# Arduino_ultrasonic_bjt.net
KiCad netlist of a schematic drawn in EAGLE
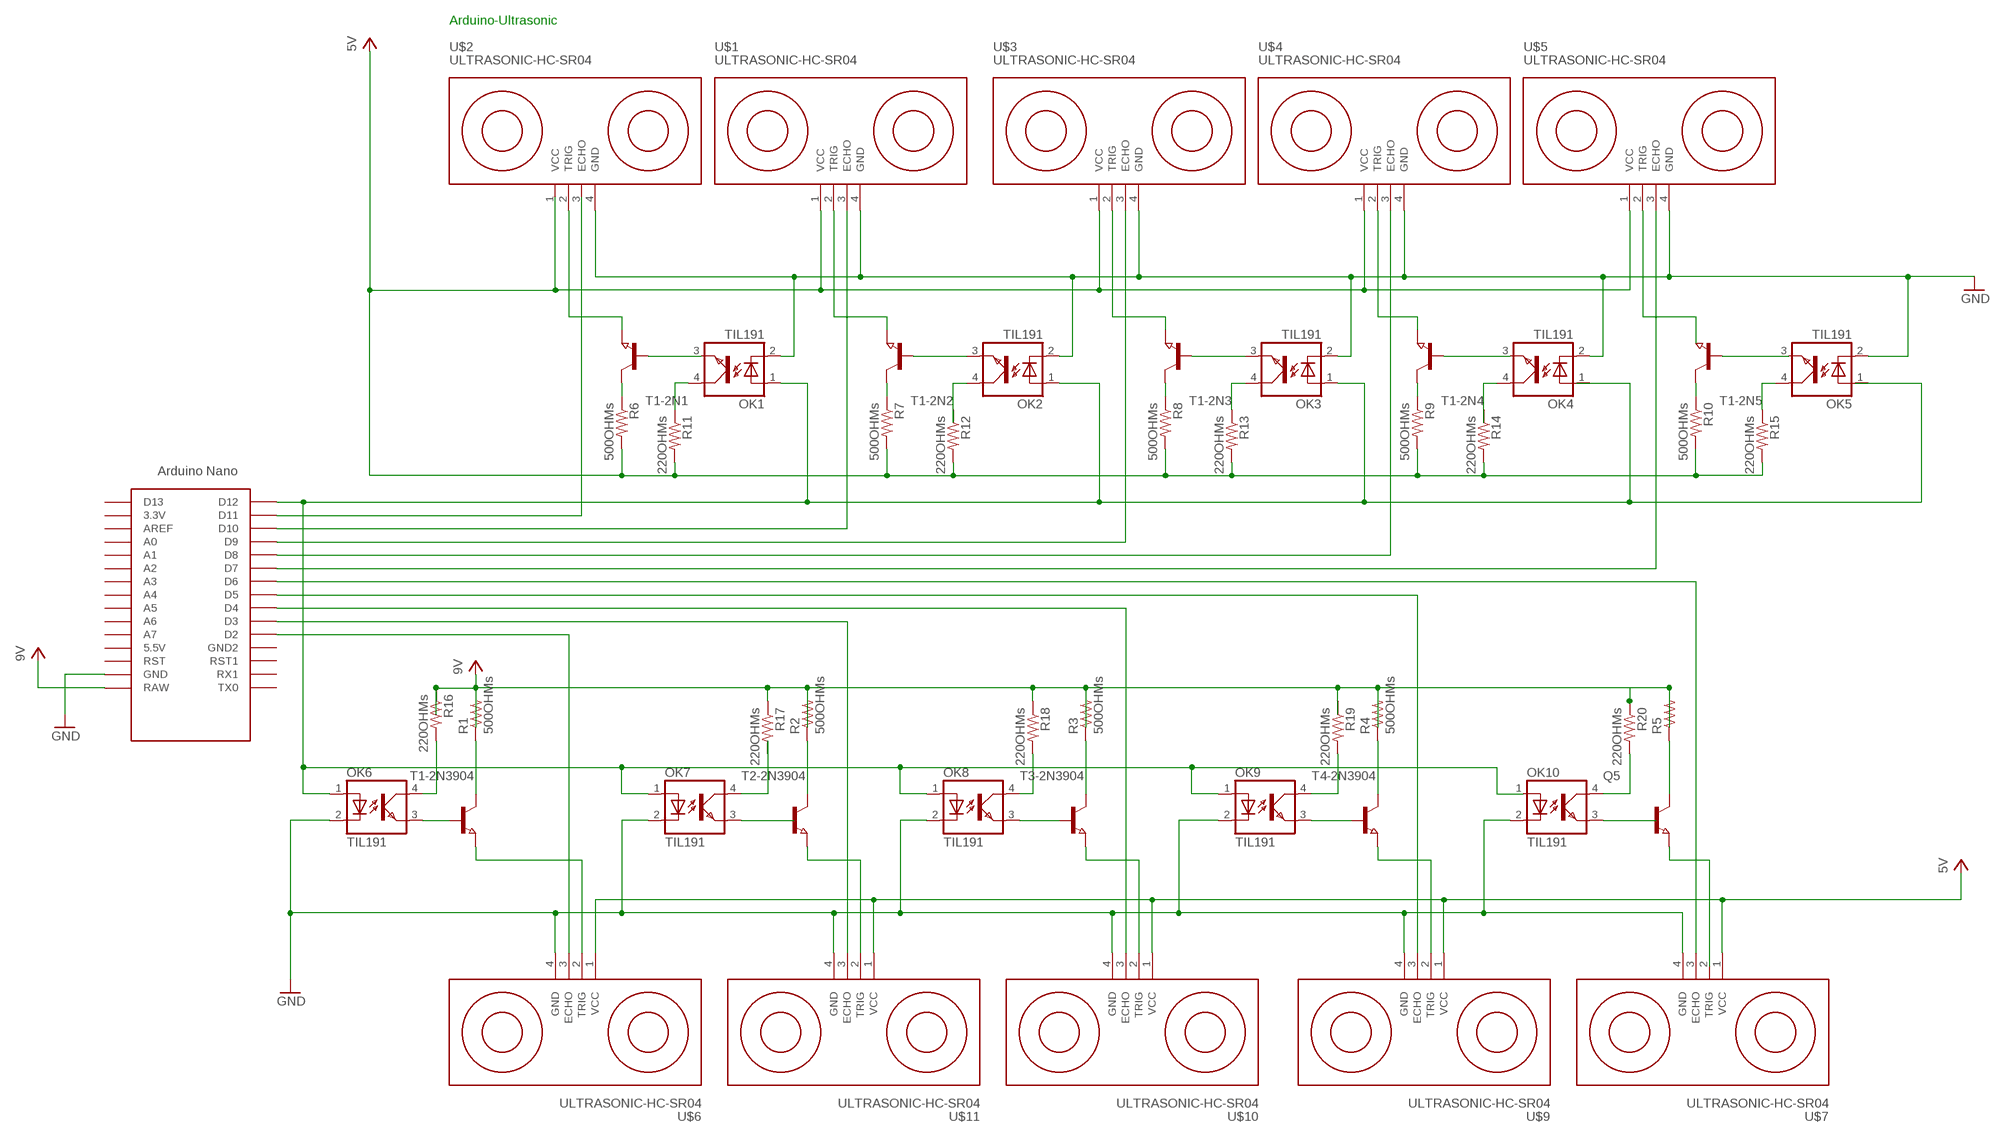
[diagram p0: schematic, sheet 1]

(export (version "E")
  (design (tool "Eeschema 10.0.6"))
  (components
    (comp (ref "OK1")
      (value "TIL191")
      (footprint "eagle-import:DIL04")
      (libsource (lib "eagle-import") (part "TIL191"))
    )
    (comp (ref "OK2")
      (value "TIL191")
      (footprint "eagle-import:DIL04")
      (libsource (lib "eagle-import") (part "TIL191"))
    )
    (comp (ref "OK3")
      (value "TIL191")
      (footprint "eagle-import:DIL04")
      (libsource (lib "eagle-import") (part "TIL191"))
    )
    (comp (ref "OK4")
      (value "TIL191")
      (footprint "eagle-import:DIL04")
      (libsource (lib "eagle-import") (part "TIL191"))
    )
    (comp (ref "OK5")
      (value "TIL191")
      (footprint "eagle-import:DIL04")
      (libsource (lib "eagle-import") (part "TIL191"))
    )
    (comp (ref "OK6")
      (value "TIL191")
      (footprint "eagle-import:DIL04")
      (libsource (lib "eagle-import") (part "TIL191"))
    )
    (comp (ref "OK7")
      (value "TIL191")
      (footprint "eagle-import:DIL04")
      (libsource (lib "eagle-import") (part "TIL191"))
    )
    (comp (ref "OK8")
      (value "TIL191")
      (footprint "eagle-import:DIL04")
      (libsource (lib "eagle-import") (part "TIL191"))
    )
    (comp (ref "OK9")
      (value "TIL191")
      (footprint "eagle-import:DIL04")
      (libsource (lib "eagle-import") (part "TIL191"))
    )
    (comp (ref "OK10")
      (value "TIL191")
      (footprint "eagle-import:DIL04")
      (libsource (lib "eagle-import") (part "TIL191"))
    )
    (comp (ref "Q5")
      (value "NPN-TRANSISTOR_SOT23")
      (footprint "eagle-import:SOT23")
      (libsource (lib "eagle-import") (part "NPN-TRANSISTOR_SOT23"))
    )
    (comp (ref "R1")
      (value "500OHMs")
      (footprint "eagle-import:0204V")
      (libsource (lib "eagle-import") (part "R-US_0204/2V"))
    )
    (comp (ref "R2")
      (value "500OHMs")
      (footprint "eagle-import:0204V")
      (libsource (lib "eagle-import") (part "R-US_0204/2V"))
    )
    (comp (ref "R3")
      (value "500OHMs")
      (footprint "eagle-import:0204V")
      (libsource (lib "eagle-import") (part "R-US_0204/2V"))
    )
    (comp (ref "R4")
      (value "500OHMs")
      (footprint "eagle-import:0204V")
      (libsource (lib "eagle-import") (part "R-US_0204/2V"))
    )
    (comp (ref "R5")
      (value "R-US_0204/2V")
      (footprint "eagle-import:0204V")
      (libsource (lib "eagle-import") (part "R-US_0204/2V"))
    )
    (comp (ref "R6")
      (value "500OHMs")
      (footprint "eagle-import:0204V")
      (libsource (lib "eagle-import") (part "R-US_0204/2V"))
    )
    (comp (ref "R7")
      (value "500OHMs")
      (footprint "eagle-import:0204V")
      (libsource (lib "eagle-import") (part "R-US_0204/2V"))
    )
    (comp (ref "R8")
      (value "500OHMs")
      (footprint "eagle-import:0204V")
      (libsource (lib "eagle-import") (part "R-US_0204/2V"))
    )
    (comp (ref "R9")
      (value "500OHMs")
      (footprint "eagle-import:0204V")
      (libsource (lib "eagle-import") (part "R-US_0204/2V"))
    )
    (comp (ref "R10")
      (value "500OHMs")
      (footprint "eagle-import:0204V")
      (libsource (lib "eagle-import") (part "R-US_0204/2V"))
    )
    (comp (ref "R11")
      (value "220OHMs")
      (footprint "eagle-import:0204V")
      (libsource (lib "eagle-import") (part "R-US_0204/2V"))
    )
    (comp (ref "R12")
      (value "220OHMs")
      (footprint "eagle-import:0204V")
      (libsource (lib "eagle-import") (part "R-US_0204/2V"))
    )
    (comp (ref "R13")
      (value "220OHMs")
      (footprint "eagle-import:0204V")
      (libsource (lib "eagle-import") (part "R-US_0204/2V"))
    )
    (comp (ref "R14")
      (value "220OHMs")
      (footprint "eagle-import:0204V")
      (libsource (lib "eagle-import") (part "R-US_0204/2V"))
    )
    (comp (ref "R15")
      (value "220OHMs")
      (footprint "eagle-import:0204V")
      (libsource (lib "eagle-import") (part "R-US_0204/2V"))
    )
    (comp (ref "R16")
      (value "220OHMs")
      (footprint "eagle-import:0204V")
      (libsource (lib "eagle-import") (part "R-US_0204/2V"))
    )
    (comp (ref "R17")
      (value "220OHMs")
      (footprint "eagle-import:0204V")
      (libsource (lib "eagle-import") (part "R-US_0204/2V"))
    )
    (comp (ref "R18")
      (value "220OHMs")
      (footprint "eagle-import:0204V")
      (libsource (lib "eagle-import") (part "R-US_0204/2V"))
    )
    (comp (ref "R19")
      (value "220OHMs")
      (footprint "eagle-import:0204V")
      (libsource (lib "eagle-import") (part "R-US_0204/2V"))
    )
    (comp (ref "R20")
      (value "220OHMs")
      (footprint "eagle-import:0204V")
      (libsource (lib "eagle-import") (part "R-US_0204/2V"))
    )
    (comp (ref "T1-2N1")
      (value "NPN-TRANSISTOR_SOT23")
      (footprint "eagle-import:SOT23")
      (libsource (lib "eagle-import") (part "NPN-TRANSISTOR_SOT23"))
    )
    (comp (ref "T1-2N2")
      (value "NPN-TRANSISTOR_SOT23")
      (footprint "eagle-import:SOT23")
      (libsource (lib "eagle-import") (part "NPN-TRANSISTOR_SOT23"))
    )
    (comp (ref "T1-2N3")
      (value "NPN-TRANSISTOR_SOT23")
      (footprint "eagle-import:SOT23")
      (libsource (lib "eagle-import") (part "NPN-TRANSISTOR_SOT23"))
    )
    (comp (ref "T1-2N4")
      (value "NPN-TRANSISTOR_SOT23")
      (footprint "eagle-import:SOT23")
      (libsource (lib "eagle-import") (part "NPN-TRANSISTOR_SOT23"))
    )
    (comp (ref "T1-2N5")
      (value "NPN-TRANSISTOR_SOT23")
      (footprint "eagle-import:SOT23")
      (libsource (lib "eagle-import") (part "NPN-TRANSISTOR_SOT23"))
    )
    (comp (ref "T1-2N3904")
      (value "NPN-TRANSISTOR_SOT23")
      (footprint "eagle-import:SOT23")
      (libsource (lib "eagle-import") (part "NPN-TRANSISTOR_SOT23"))
    )
    (comp (ref "T2-2N3904")
      (value "NPN-TRANSISTOR_SOT23")
      (footprint "eagle-import:SOT23")
      (libsource (lib "eagle-import") (part "NPN-TRANSISTOR_SOT23"))
    )
    (comp (ref "T3-2N3904")
      (value "NPN-TRANSISTOR_SOT23")
      (footprint "eagle-import:SOT23")
      (libsource (lib "eagle-import") (part "NPN-TRANSISTOR_SOT23"))
    )
    (comp (ref "T4-2N3904")
      (value "NPN-TRANSISTOR_SOT23")
      (footprint "eagle-import:SOT23")
      (libsource (lib "eagle-import") (part "NPN-TRANSISTOR_SOT23"))
    )
    (comp (ref "U$1")
      (value "ULTRASONIC-HC-SR04")
      (footprint "eagle-import:ULTRASONIC-HC-SR04")
      (libsource (lib "eagle-import") (part "ULTRASONIC-HC-SR04"))
    )
    (comp (ref "U$2")
      (value "ULTRASONIC-HC-SR04")
      (footprint "eagle-import:ULTRASONIC-HC-SR04")
      (libsource (lib "eagle-import") (part "ULTRASONIC-HC-SR04"))
    )
    (comp (ref "U$3")
      (value "ULTRASONIC-HC-SR04")
      (footprint "eagle-import:ULTRASONIC-HC-SR04")
      (libsource (lib "eagle-import") (part "ULTRASONIC-HC-SR04"))
    )
    (comp (ref "U$4")
      (value "ULTRASONIC-HC-SR04")
      (footprint "eagle-import:ULTRASONIC-HC-SR04")
      (libsource (lib "eagle-import") (part "ULTRASONIC-HC-SR04"))
    )
    (comp (ref "U$5")
      (value "ULTRASONIC-HC-SR04")
      (footprint "eagle-import:ULTRASONIC-HC-SR04")
      (libsource (lib "eagle-import") (part "ULTRASONIC-HC-SR04"))
    )
    (comp (ref "U$6")
      (value "ULTRASONIC-HC-SR04")
      (footprint "eagle-import:ULTRASONIC-HC-SR04")
      (libsource (lib "eagle-import") (part "ULTRASONIC-HC-SR04"))
    )
    (comp (ref "U$7")
      (value "ULTRASONIC-HC-SR04")
      (footprint "eagle-import:ULTRASONIC-HC-SR04")
      (libsource (lib "eagle-import") (part "ULTRASONIC-HC-SR04"))
    )
    (comp (ref "U$9")
      (value "ULTRASONIC-HC-SR04")
      (footprint "eagle-import:ULTRASONIC-HC-SR04")
      (libsource (lib "eagle-import") (part "ULTRASONIC-HC-SR04"))
    )
    (comp (ref "U$10")
      (value "ULTRASONIC-HC-SR04")
      (footprint "eagle-import:ULTRASONIC-HC-SR04")
      (libsource (lib "eagle-import") (part "ULTRASONIC-HC-SR04"))
    )
    (comp (ref "U$11")
      (value "ULTRASONIC-HC-SR04")
      (footprint "eagle-import:ULTRASONIC-HC-SR04")
      (libsource (lib "eagle-import") (part "ULTRASONIC-HC-SR04"))
    )
    (comp (ref "U$12")
      (value "NANO")
      (footprint "eagle-import:NANO")
      (libsource (lib "eagle-import") (part "NANO"))
    )
  )
  (nets
    (net (code "1") (name "5V") (class "Default")
      (node (ref "R1") (pin "2") (pinfunction "2_2") (pintype "passive"))
      (node (ref "R10") (pin "2") (pinfunction "2_2") (pintype "passive"))
      (node (ref "R11") (pin "2") (pinfunction "2_2") (pintype "passive"))
      (node (ref "R12") (pin "2") (pinfunction "2_2") (pintype "passive"))
      (node (ref "R13") (pin "2") (pinfunction "2_2") (pintype "passive"))
      (node (ref "R14") (pin "2") (pinfunction "2_2") (pintype "passive"))
      (node (ref "R15") (pin "2") (pinfunction "2_2") (pintype "passive"))
      (node (ref "R16") (pin "1") (pinfunction "1_1") (pintype "passive"))
      (node (ref "R17") (pin "1") (pinfunction "1_1") (pintype "passive"))
      (node (ref "R18") (pin "1") (pinfunction "1_1") (pintype "passive"))
      (node (ref "R2") (pin "2") (pinfunction "2_2") (pintype "passive"))
      (node (ref "R20") (pin "1") (pinfunction "1_1") (pintype "passive"))
      (node (ref "R3") (pin "2") (pinfunction "2_2") (pintype "passive"))
      (node (ref "R4") (pin "2") (pinfunction "2_2") (pintype "passive"))
      (node (ref "R5") (pin "2") (pinfunction "2_2") (pintype "passive"))
      (node (ref "R6") (pin "2") (pinfunction "2_2") (pintype "passive"))
      (node (ref "R7") (pin "2") (pinfunction "2_2") (pintype "passive"))
      (node (ref "R8") (pin "2") (pinfunction "2_2") (pintype "passive"))
      (node (ref "R9") (pin "2") (pinfunction "2_2") (pintype "passive"))
      (node (ref "U$1") (pin "1") (pinfunction "VCC_1") (pintype "power_in"))
      (node (ref "U$10") (pin "1") (pinfunction "VCC_1") (pintype "power_in"))
      (node (ref "U$11") (pin "1") (pinfunction "VCC_1") (pintype "power_in"))
      (node (ref "U$12") (pin "RAW") (pinfunction "RAW_RAW") (pintype "bidirectional"))
      (node (ref "U$2") (pin "1") (pinfunction "VCC_1") (pintype "power_in"))
      (node (ref "U$3") (pin "1") (pinfunction "VCC_1") (pintype "power_in"))
      (node (ref "U$4") (pin "1") (pinfunction "VCC_1") (pintype "power_in"))
      (node (ref "U$5") (pin "1") (pinfunction "VCC_1") (pintype "power_in"))
      (node (ref "U$6") (pin "1") (pinfunction "VCC_1") (pintype "power_in"))
      (node (ref "U$7") (pin "1") (pinfunction "VCC_1") (pintype "power_in"))
      (node (ref "U$9") (pin "1") (pinfunction "VCC_1") (pintype "power_in"))
    )
    (net (code "2") (name "GND") (class "Default")
      (node (ref "OK1") (pin "2") (pinfunction "C_2") (pintype "passive"))
      (node (ref "OK10") (pin "2") (pinfunction "C_2") (pintype "passive"))
      (node (ref "OK2") (pin "2") (pinfunction "C_2") (pintype "passive"))
      (node (ref "OK3") (pin "2") (pinfunction "C_2") (pintype "passive"))
      (node (ref "OK4") (pin "2") (pinfunction "C_2") (pintype "passive"))
      (node (ref "OK5") (pin "2") (pinfunction "C_2") (pintype "passive"))
      (node (ref "OK6") (pin "2") (pinfunction "C_2") (pintype "passive"))
      (node (ref "OK7") (pin "2") (pinfunction "C_2") (pintype "passive"))
      (node (ref "OK8") (pin "2") (pinfunction "C_2") (pintype "passive"))
      (node (ref "OK9") (pin "2") (pinfunction "C_2") (pintype "passive"))
      (node (ref "U$1") (pin "4") (pinfunction "GND_4") (pintype "power_in"))
      (node (ref "U$10") (pin "4") (pinfunction "GND_4") (pintype "power_in"))
      (node (ref "U$11") (pin "4") (pinfunction "GND_4") (pintype "power_in"))
      (node (ref "U$12") (pin "GND") (pinfunction "GND_GND") (pintype "bidirectional"))
      (node (ref "U$2") (pin "4") (pinfunction "GND_4") (pintype "power_in"))
      (node (ref "U$3") (pin "4") (pinfunction "GND_4") (pintype "power_in"))
      (node (ref "U$4") (pin "4") (pinfunction "GND_4") (pintype "power_in"))
      (node (ref "U$5") (pin "4") (pinfunction "GND_4") (pintype "power_in"))
      (node (ref "U$6") (pin "4") (pinfunction "GND_4") (pintype "power_in"))
      (node (ref "U$7") (pin "4") (pinfunction "GND_4") (pintype "power_in"))
      (node (ref "U$9") (pin "4") (pinfunction "GND_4") (pintype "power_in"))
    )
    (net (code "3") (name "Net-(OK1-A)") (class "Default")
      (node (ref "OK1") (pin "1") (pinfunction "A_1") (pintype "passive"))
      (node (ref "OK2") (pin "1") (pinfunction "A_1") (pintype "passive"))
      (node (ref "OK3") (pin "1") (pinfunction "A_1") (pintype "passive"))
      (node (ref "OK6") (pin "1") (pinfunction "A_1") (pintype "passive"))
      (node (ref "OK7") (pin "1") (pinfunction "A_1") (pintype "passive"))
      (node (ref "OK8") (pin "1") (pinfunction "A_1") (pintype "passive"))
      (node (ref "OK9") (pin "1") (pinfunction "A_1") (pintype "passive"))
      (node (ref "U$12") (pin "D12") (pinfunction "D12_D12") (pintype "bidirectional"))
    )
    (net (code "4") (name "Net-(OK1-COL)") (class "Default")
      (node (ref "OK1") (pin "4") (pinfunction "COL_4") (pintype "passive"))
      (node (ref "R11") (pin "1") (pinfunction "1_1") (pintype "passive"))
    )
    (net (code "5") (name "Net-(OK2-EMIT)") (class "Default")
      (node (ref "OK2") (pin "3") (pinfunction "EMIT_3") (pintype "passive"))
      (node (ref "T1-2N2") (pin "1") (pinfunction "B_1") (pintype "passive"))
    )
    (net (code "6") (name "Net-(OK3-COL)") (class "Default")
      (node (ref "OK3") (pin "4") (pinfunction "COL_4") (pintype "passive"))
      (node (ref "R13") (pin "1") (pinfunction "1_1") (pintype "passive"))
    )
    (net (code "7") (name "Net-(OK3-EMIT)") (class "Default")
      (node (ref "OK3") (pin "3") (pinfunction "EMIT_3") (pintype "passive"))
      (node (ref "T1-2N3") (pin "1") (pinfunction "B_1") (pintype "passive"))
    )
    (net (code "8") (name "Net-(OK5-COL)") (class "Default")
      (node (ref "OK5") (pin "4") (pinfunction "COL_4") (pintype "passive"))
      (node (ref "R15") (pin "1") (pinfunction "1_1") (pintype "passive"))
    )
    (net (code "9") (name "Net-(OK6-COL)") (class "Default")
      (node (ref "OK6") (pin "4") (pinfunction "COL_4") (pintype "passive"))
      (node (ref "R16") (pin "2") (pinfunction "2_2") (pintype "passive"))
    )
    (net (code "10") (name "Net-(OK6-EMIT)") (class "Default")
      (node (ref "OK6") (pin "3") (pinfunction "EMIT_3") (pintype "passive"))
      (node (ref "T1-2N3904") (pin "1") (pinfunction "B_1") (pintype "passive"))
    )
    (net (code "11") (name "Net-(OK8-COL)") (class "Default")
      (node (ref "OK8") (pin "4") (pinfunction "COL_4") (pintype "passive"))
      (node (ref "R18") (pin "2") (pinfunction "2_2") (pintype "passive"))
    )
    (net (code "12") (name "Net-(OK8-EMIT)") (class "Default")
      (node (ref "OK8") (pin "3") (pinfunction "EMIT_3") (pintype "passive"))
      (node (ref "T3-2N3904") (pin "1") (pinfunction "B_1") (pintype "passive"))
    )
    (net (code "13") (name "Net-(OK9-COL)") (class "Default")
      (node (ref "OK9") (pin "4") (pinfunction "COL_4") (pintype "passive"))
      (node (ref "R19") (pin "2") (pinfunction "2_2") (pintype "passive"))
    )
    (net (code "14") (name "Net-(OK9-EMIT)") (class "Default")
      (node (ref "OK9") (pin "3") (pinfunction "EMIT_3") (pintype "passive"))
      (node (ref "T4-2N3904") (pin "1") (pinfunction "B_1") (pintype "passive"))
    )
    (net (code "15") (name "Net-(OK10-COL)") (class "Default")
      (node (ref "OK10") (pin "4") (pinfunction "COL_4") (pintype "passive"))
      (node (ref "R20") (pin "2") (pinfunction "2_2") (pintype "passive"))
    )
    (net (code "16") (name "Net-(Q5-C)") (class "Default")
      (node (ref "Q5") (pin "3") (pinfunction "C_3") (pintype "passive"))
      (node (ref "R5") (pin "1") (pinfunction "1_1") (pintype "passive"))
    )
    (net (code "17") (name "Net-(T1-2N1-C)") (class "Default")
      (node (ref "R6") (pin "1") (pinfunction "1_1") (pintype "passive"))
      (node (ref "T1-2N1") (pin "3") (pinfunction "C_3") (pintype "passive"))
    )
    (net (code "18") (name "Net-(T1-2N1-E)") (class "Default")
      (node (ref "T1-2N1") (pin "2") (pinfunction "E_2") (pintype "passive"))
      (node (ref "U$2") (pin "2") (pinfunction "TRIG_2") (pintype "input"))
    )
    (net (code "19") (name "Net-(T1-2N2-C)") (class "Default")
      (node (ref "R7") (pin "1") (pinfunction "1_1") (pintype "passive"))
      (node (ref "T1-2N2") (pin "3") (pinfunction "C_3") (pintype "passive"))
    )
    (net (code "20") (name "Net-(T1-2N2-E)") (class "Default")
      (node (ref "T1-2N2") (pin "2") (pinfunction "E_2") (pintype "passive"))
      (node (ref "U$1") (pin "2") (pinfunction "TRIG_2") (pintype "input"))
    )
    (net (code "21") (name "Net-(T1-2N3-C)") (class "Default")
      (node (ref "R8") (pin "1") (pinfunction "1_1") (pintype "passive"))
      (node (ref "T1-2N3") (pin "3") (pinfunction "C_3") (pintype "passive"))
    )
    (net (code "22") (name "Net-(T1-2N3-E)") (class "Default")
      (node (ref "T1-2N3") (pin "2") (pinfunction "E_2") (pintype "passive"))
      (node (ref "U$3") (pin "2") (pinfunction "TRIG_2") (pintype "input"))
    )
    (net (code "23") (name "Net-(T1-2N4-C)") (class "Default")
      (node (ref "R9") (pin "1") (pinfunction "1_1") (pintype "passive"))
      (node (ref "T1-2N4") (pin "3") (pinfunction "C_3") (pintype "passive"))
    )
    (net (code "24") (name "Net-(T1-2N4-E)") (class "Default")
      (node (ref "T1-2N4") (pin "2") (pinfunction "E_2") (pintype "passive"))
      (node (ref "U$4") (pin "2") (pinfunction "TRIG_2") (pintype "input"))
    )
    (net (code "25") (name "Net-(T1-2N5-C)") (class "Default")
      (node (ref "R10") (pin "1") (pinfunction "1_1") (pintype "passive"))
      (node (ref "T1-2N5") (pin "3") (pinfunction "C_3") (pintype "passive"))
    )
    (net (code "26") (name "Net-(T1-2N3904-C)") (class "Default")
      (node (ref "R1") (pin "1") (pinfunction "1_1") (pintype "passive"))
      (node (ref "T1-2N3904") (pin "3") (pinfunction "C_3") (pintype "passive"))
    )
    (net (code "27") (name "Net-(T1-2N3904-E)") (class "Default")
      (node (ref "T1-2N3904") (pin "2") (pinfunction "E_2") (pintype "passive"))
      (node (ref "U$6") (pin "2") (pinfunction "TRIG_2") (pintype "input"))
    )
    (net (code "28") (name "Net-(T2-2N3904-C)") (class "Default")
      (node (ref "R2") (pin "1") (pinfunction "1_1") (pintype "passive"))
      (node (ref "T2-2N3904") (pin "3") (pinfunction "C_3") (pintype "passive"))
    )
    (net (code "29") (name "Net-(T2-2N3904-E)") (class "Default")
      (node (ref "T2-2N3904") (pin "2") (pinfunction "E_2") (pintype "passive"))
      (node (ref "U$11") (pin "2") (pinfunction "TRIG_2") (pintype "input"))
    )
    (net (code "30") (name "Net-(T3-2N3904-C)") (class "Default")
      (node (ref "R3") (pin "1") (pinfunction "1_1") (pintype "passive"))
      (node (ref "T3-2N3904") (pin "3") (pinfunction "C_3") (pintype "passive"))
    )
    (net (code "31") (name "Net-(T3-2N3904-E)") (class "Default")
      (node (ref "T3-2N3904") (pin "2") (pinfunction "E_2") (pintype "passive"))
      (node (ref "U$10") (pin "2") (pinfunction "TRIG_2") (pintype "input"))
    )
    (net (code "32") (name "Net-(T4-2N3904-C)") (class "Default")
      (node (ref "R4") (pin "1") (pinfunction "1_1") (pintype "passive"))
      (node (ref "T4-2N3904") (pin "3") (pinfunction "C_3") (pintype "passive"))
    )
    (net (code "33") (name "Net-(T4-2N3904-E)") (class "Default")
      (node (ref "T4-2N3904") (pin "2") (pinfunction "E_2") (pintype "passive"))
      (node (ref "U$9") (pin "2") (pinfunction "TRIG_2") (pintype "input"))
    )
    (net (code "34") (name "Net-(U$1-ECHO)") (class "Default")
      (node (ref "U$1") (pin "3") (pinfunction "ECHO_3") (pintype "output"))
      (node (ref "U$12") (pin "D10") (pinfunction "D10_D10") (pintype "bidirectional"))
    )
    (net (code "35") (name "Net-(U$2-ECHO)") (class "Default")
      (node (ref "U$12") (pin "D11") (pinfunction "D11_D11") (pintype "bidirectional"))
      (node (ref "U$2") (pin "3") (pinfunction "ECHO_3") (pintype "output"))
    )
    (net (code "36") (name "Net-(U$3-ECHO)") (class "Default")
      (node (ref "U$12") (pin "D9") (pinfunction "D9_D9") (pintype "bidirectional"))
      (node (ref "U$3") (pin "3") (pinfunction "ECHO_3") (pintype "output"))
    )
    (net (code "37") (name "Net-(U$4-ECHO)") (class "Default")
      (node (ref "U$12") (pin "D8") (pinfunction "D8_D8") (pintype "bidirectional"))
      (node (ref "U$4") (pin "3") (pinfunction "ECHO_3") (pintype "output"))
    )
    (net (code "38") (name "Net-(U$5-ECHO)") (class "Default")
      (node (ref "U$12") (pin "D7") (pinfunction "D7_D7") (pintype "bidirectional"))
      (node (ref "U$5") (pin "3") (pinfunction "ECHO_3") (pintype "output"))
    )
    (net (code "39") (name "Net-(U$6-ECHO)") (class "Default")
      (node (ref "U$12") (pin "D2") (pinfunction "D2_D2") (pintype "bidirectional"))
      (node (ref "U$6") (pin "3") (pinfunction "ECHO_3") (pintype "output"))
    )
    (net (code "40") (name "Net-(U$7-ECHO)") (class "Default")
      (node (ref "U$12") (pin "D6") (pinfunction "D6_D6") (pintype "bidirectional"))
      (node (ref "U$7") (pin "3") (pinfunction "ECHO_3") (pintype "output"))
    )
    (net (code "41") (name "Net-(U$9-ECHO)") (class "Default")
      (node (ref "U$12") (pin "D5") (pinfunction "D5_D5") (pintype "bidirectional"))
      (node (ref "U$9") (pin "3") (pinfunction "ECHO_3") (pintype "output"))
    )
    (net (code "42") (name "Net-(U$10-ECHO)") (class "Default")
      (node (ref "U$10") (pin "3") (pinfunction "ECHO_3") (pintype "output"))
      (node (ref "U$12") (pin "D4") (pinfunction "D4_D4") (pintype "bidirectional"))
    )
    (net (code "43") (name "Net-(U$11-ECHO)") (class "Default")
      (node (ref "U$11") (pin "3") (pinfunction "ECHO_3") (pintype "output"))
      (node (ref "U$12") (pin "D3") (pinfunction "D3_D3") (pintype "bidirectional"))
    )
    (net (code "44") (name "unconnected-(OK1-EMIT-Pad3)") (class "Default")
      (node (ref "OK1") (pin "3") (pinfunction "EMIT_3") (pintype "passive"))
    )
    (net (code "45") (name "unconnected-(OK2-COL-Pad4)") (class "Default")
      (node (ref "OK2") (pin "4") (pinfunction "COL_4") (pintype "passive"))
    )
    (net (code "46") (name "unconnected-(OK4-A-Pad1)") (class "Default")
      (node (ref "OK4") (pin "1") (pinfunction "A_1") (pintype "passive"))
    )
    (net (code "47") (name "unconnected-(OK4-COL-Pad4)") (class "Default")
      (node (ref "OK4") (pin "4") (pinfunction "COL_4") (pintype "passive"))
    )
    (net (code "48") (name "unconnected-(OK4-EMIT-Pad3)") (class "Default")
      (node (ref "OK4") (pin "3") (pinfunction "EMIT_3") (pintype "passive"))
    )
    (net (code "49") (name "unconnected-(OK5-A-Pad1)") (class "Default")
      (node (ref "OK5") (pin "1") (pinfunction "A_1") (pintype "passive"))
    )
    (net (code "50") (name "unconnected-(OK5-EMIT-Pad3)") (class "Default")
      (node (ref "OK5") (pin "3") (pinfunction "EMIT_3") (pintype "passive"))
    )
    (net (code "51") (name "unconnected-(OK7-COL-Pad4)") (class "Default")
      (node (ref "OK7") (pin "4") (pinfunction "COL_4") (pintype "passive"))
    )
    (net (code "52") (name "unconnected-(OK7-EMIT-Pad3)") (class "Default")
      (node (ref "OK7") (pin "3") (pinfunction "EMIT_3") (pintype "passive"))
    )
    (net (code "53") (name "unconnected-(OK10-A-Pad1)") (class "Default")
      (node (ref "OK10") (pin "1") (pinfunction "A_1") (pintype "passive"))
    )
    (net (code "54") (name "unconnected-(OK10-EMIT-Pad3)") (class "Default")
      (node (ref "OK10") (pin "3") (pinfunction "EMIT_3") (pintype "passive"))
    )
    (net (code "55") (name "unconnected-(Q5-B-Pad1)") (class "Default")
      (node (ref "Q5") (pin "1") (pinfunction "B_1") (pintype "passive"))
    )
    (net (code "56") (name "unconnected-(Q5-E-Pad2)") (class "Default")
      (node (ref "Q5") (pin "2") (pinfunction "E_2") (pintype "passive"))
    )
    (net (code "57") (name "unconnected-(R12-Pad1)") (class "Default")
      (node (ref "R12") (pin "1") (pinfunction "1_1") (pintype "passive"))
    )
    (net (code "58") (name "unconnected-(R14-Pad1)") (class "Default")
      (node (ref "R14") (pin "1") (pinfunction "1_1") (pintype "passive"))
    )
    (net (code "59") (name "unconnected-(R17-Pad2)") (class "Default")
      (node (ref "R17") (pin "2") (pinfunction "2_2") (pintype "passive"))
    )
    (net (code "60") (name "unconnected-(R19-Pad1)") (class "Default")
      (node (ref "R19") (pin "1") (pinfunction "1_1") (pintype "passive"))
    )
    (net (code "61") (name "unconnected-(T1-2N1-B-Pad1)") (class "Default")
      (node (ref "T1-2N1") (pin "1") (pinfunction "B_1") (pintype "passive"))
    )
    (net (code "62") (name "unconnected-(T1-2N4-B-Pad1)") (class "Default")
      (node (ref "T1-2N4") (pin "1") (pinfunction "B_1") (pintype "passive"))
    )
    (net (code "63") (name "unconnected-(T1-2N5-B-Pad1)") (class "Default")
      (node (ref "T1-2N5") (pin "1") (pinfunction "B_1") (pintype "passive"))
    )
    (net (code "64") (name "unconnected-(T1-2N5-E-Pad2)") (class "Default")
      (node (ref "T1-2N5") (pin "2") (pinfunction "E_2") (pintype "passive"))
    )
    (net (code "65") (name "unconnected-(T2-2N3904-B-Pad1)") (class "Default")
      (node (ref "T2-2N3904") (pin "1") (pinfunction "B_1") (pintype "passive"))
    )
    (net (code "66") (name "unconnected-(U$5-TRIG-Pad2)") (class "Default")
      (node (ref "U$5") (pin "2") (pinfunction "TRIG_2") (pintype "input"))
    )
    (net (code "67") (name "unconnected-(U$7-TRIG-Pad2)") (class "Default")
      (node (ref "U$7") (pin "2") (pinfunction "TRIG_2") (pintype "input"))
    )
    (net (code "68") (name "unconnected-(U$12-5.5V-Pad5V)") (class "Default")
      (node (ref "U$12") (pin "5V") (pinfunction "5.5V_5V") (pintype "bidirectional"))
    )
    (net (code "69") (name "unconnected-(U$12-GND2-PadGND1)") (class "Default")
      (node (ref "U$12") (pin "GND1") (pinfunction "GND2_GND1") (pintype "bidirectional"))
    )
    (net (code "70") (name "unconnected-(U$12-Pad3.3V)") (class "Default")
      (node (ref "U$12") (pin "3.3V") (pinfunction "3.3V_3.3V") (pintype "bidirectional"))
    )
    (net (code "71") (name "unconnected-(U$12-PadA0)") (class "Default")
      (node (ref "U$12") (pin "A0") (pinfunction "A0_A0") (pintype "bidirectional"))
    )
    (net (code "72") (name "unconnected-(U$12-PadA1)") (class "Default")
      (node (ref "U$12") (pin "A1") (pinfunction "A1_A1") (pintype "bidirectional"))
    )
    (net (code "73") (name "unconnected-(U$12-PadA2)") (class "Default")
      (node (ref "U$12") (pin "A2") (pinfunction "A2_A2") (pintype "bidirectional"))
    )
    (net (code "74") (name "unconnected-(U$12-PadA3)") (class "Default")
      (node (ref "U$12") (pin "A3") (pinfunction "A3_A3") (pintype "bidirectional"))
    )
    (net (code "75") (name "unconnected-(U$12-PadA4)") (class "Default")
      (node (ref "U$12") (pin "A4") (pinfunction "A4_A4") (pintype "bidirectional"))
    )
    (net (code "76") (name "unconnected-(U$12-PadA5)") (class "Default")
      (node (ref "U$12") (pin "A5") (pinfunction "A5_A5") (pintype "bidirectional"))
    )
    (net (code "77") (name "unconnected-(U$12-PadA6)") (class "Default")
      (node (ref "U$12") (pin "A6") (pinfunction "A6_A6") (pintype "bidirectional"))
    )
    (net (code "78") (name "unconnected-(U$12-PadA7)") (class "Default")
      (node (ref "U$12") (pin "A7") (pinfunction "A7_A7") (pintype "bidirectional"))
    )
    (net (code "79") (name "unconnected-(U$12-PadAREF)") (class "Default")
      (node (ref "U$12") (pin "AREF") (pinfunction "AREF_AREF") (pintype "bidirectional"))
    )
    (net (code "80") (name "unconnected-(U$12-PadD13)") (class "Default")
      (node (ref "U$12") (pin "D13") (pinfunction "D13_D13") (pintype "bidirectional"))
    )
    (net (code "81") (name "unconnected-(U$12-PadICSP1)") (class "Default")
      (node (ref "U$12") (pin "ICSP1") (pinfunction "ICSP1_ICSP1") (pintype "bidirectional"))
    )
    (net (code "82") (name "unconnected-(U$12-PadICSP2)") (class "Default")
      (node (ref "U$12") (pin "ICSP2") (pinfunction "ICSP2_ICSP2") (pintype "bidirectional"))
    )
    (net (code "83") (name "unconnected-(U$12-PadICSP3)") (class "Default")
      (node (ref "U$12") (pin "ICSP3") (pinfunction "ICSP3_ICSP3") (pintype "bidirectional"))
    )
    (net (code "84") (name "unconnected-(U$12-PadICSP4)") (class "Default")
      (node (ref "U$12") (pin "ICSP4") (pinfunction "ICSP4_ICSP4") (pintype "bidirectional"))
    )
    (net (code "85") (name "unconnected-(U$12-PadICSP5)") (class "Default")
      (node (ref "U$12") (pin "ICSP5") (pinfunction "ICSP5_ICSP5") (pintype "bidirectional"))
    )
    (net (code "86") (name "unconnected-(U$12-PadICSP6)") (class "Default")
      (node (ref "U$12") (pin "ICSP6") (pinfunction "ICSP6_ICSP6") (pintype "bidirectional"))
    )
    (net (code "87") (name "unconnected-(U$12-PadRST)") (class "Default")
      (node (ref "U$12") (pin "RST") (pinfunction "RST_RST") (pintype "bidirectional"))
    )
    (net (code "88") (name "unconnected-(U$12-PadRST1)") (class "Default")
      (node (ref "U$12") (pin "RST1") (pinfunction "RST1_RST1") (pintype "bidirectional"))
    )
    (net (code "89") (name "unconnected-(U$12-PadRX1)") (class "Default")
      (node (ref "U$12") (pin "RX1") (pinfunction "RX1_RX1") (pintype "bidirectional"))
    )
    (net (code "90") (name "unconnected-(U$12-PadTX0)") (class "Default")
      (node (ref "U$12") (pin "TX0") (pinfunction "TX0_TX0") (pintype "bidirectional"))
    )
  )
)
